# Reflectometer_Sheet.net
KiCad netlist of a schematic drawn in Altium Designer
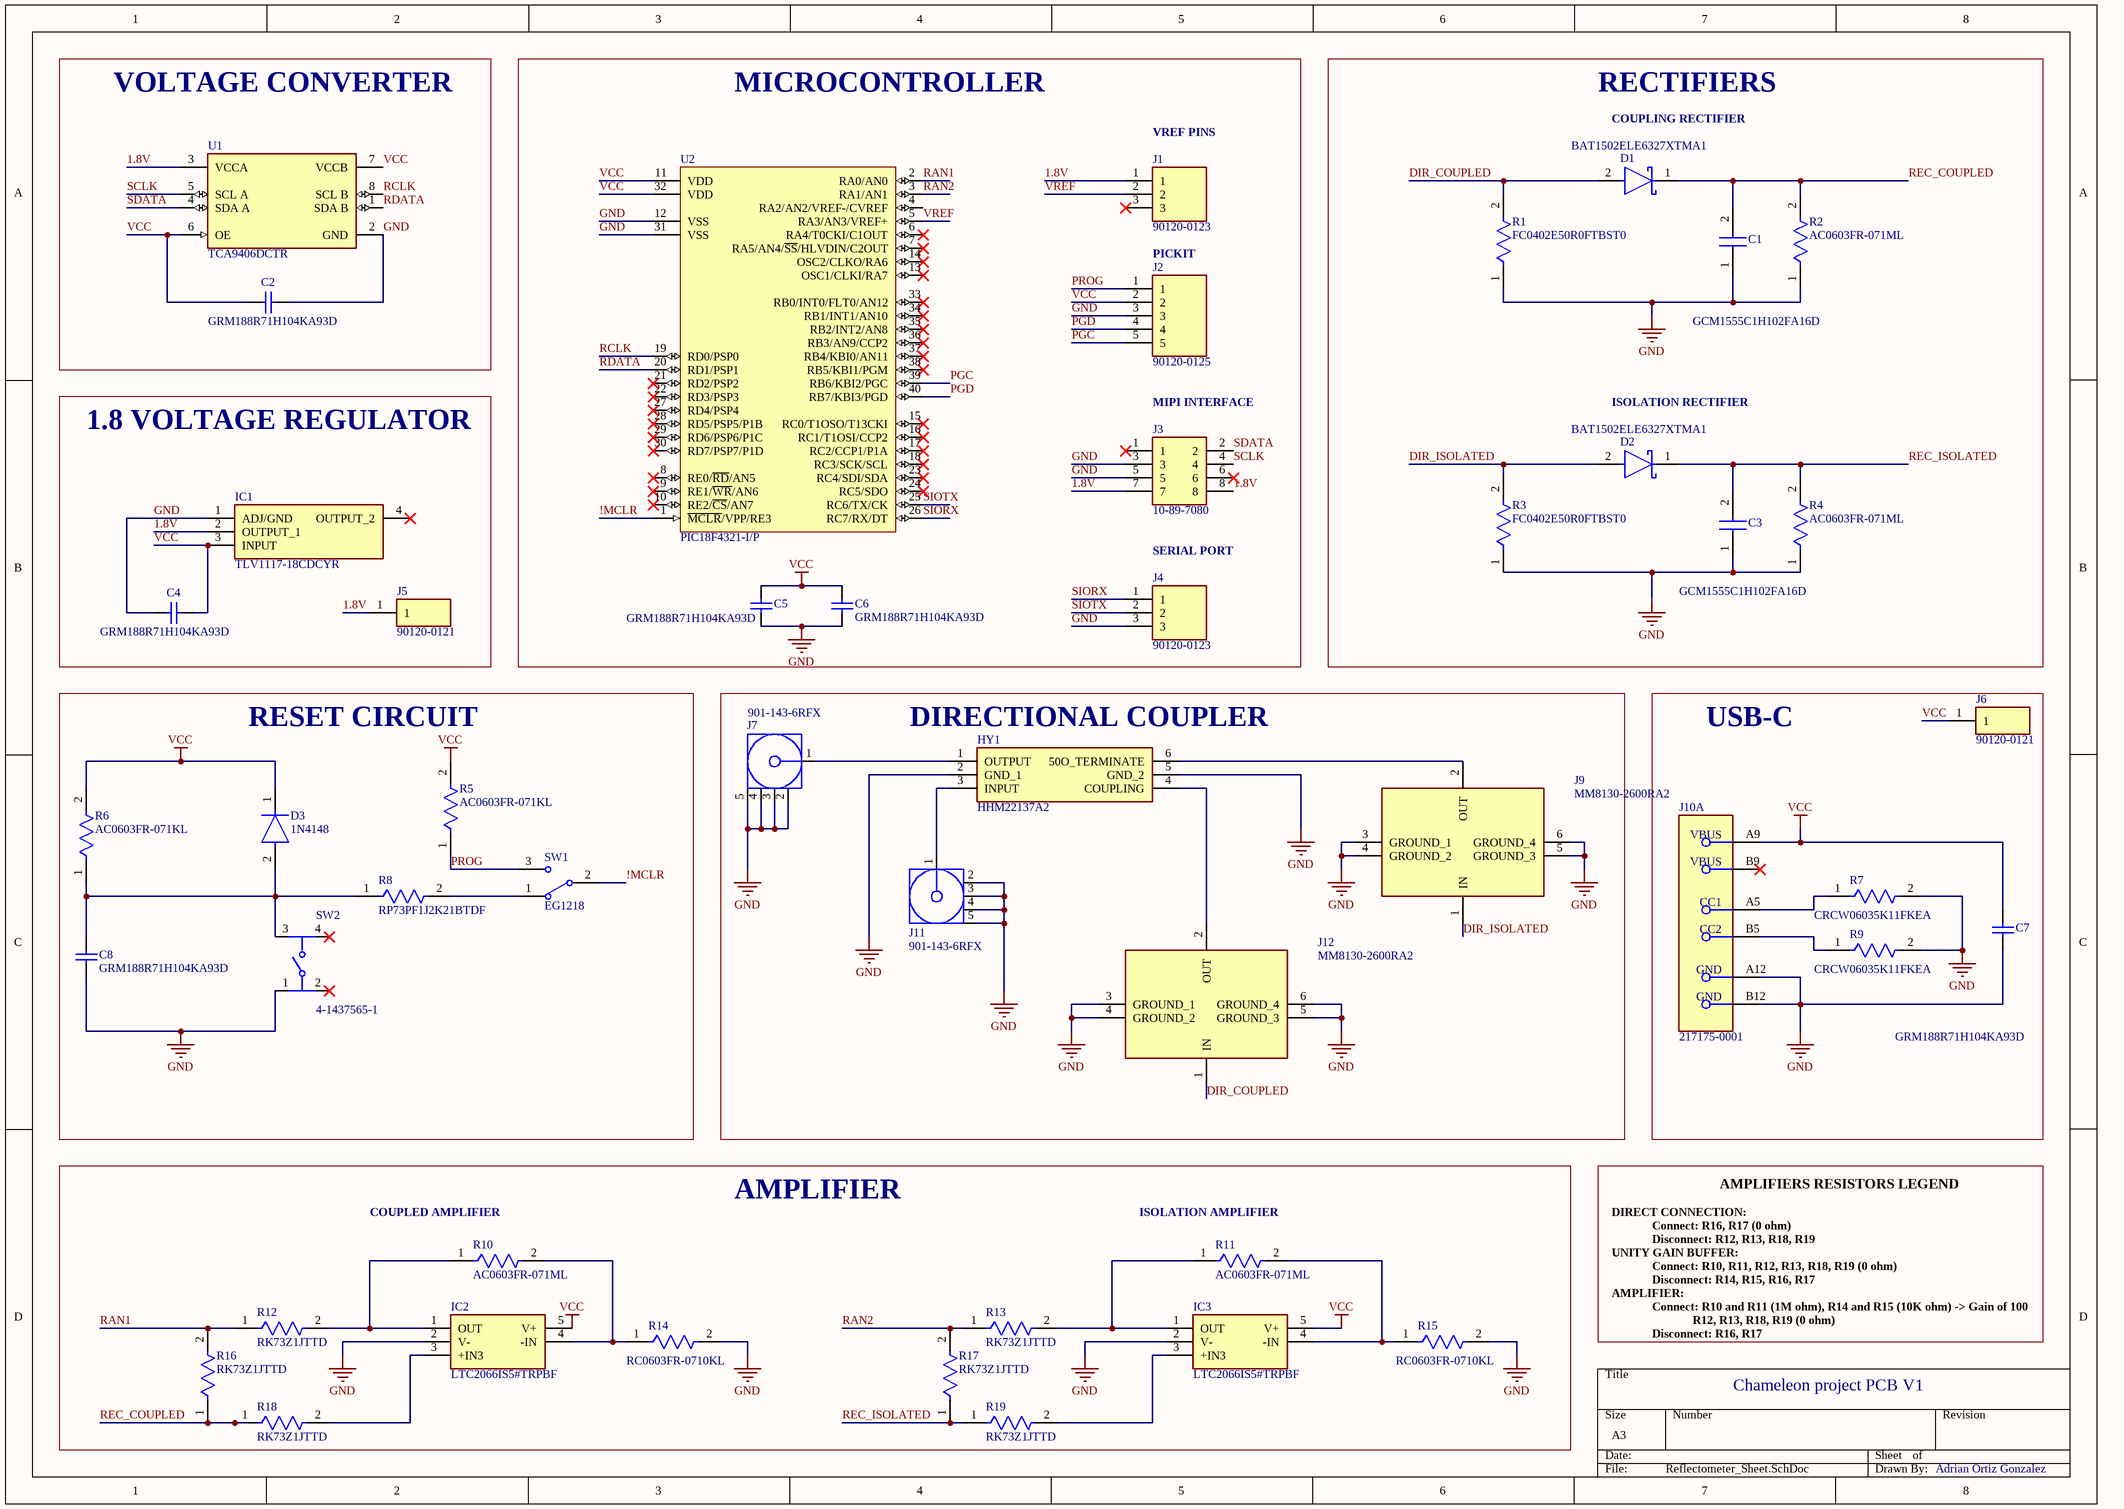
[diagram p0: Reflectometer_Sheet.SchDoc]

(export (version "E")
  (design (tool "Eeschema 10.0.6"))
  (components
    (comp (ref "C1")
      (value "GCM1555C1H102FA16D")
      (footprint "SamacSys:GCM155")
      (description "Capacitor")
      (fields (field (name "MOUSER PART NUMBER") "81-GCM1555C1H102FA6D"))
      (libsource (lib "*") (part "GCM1555C1H102FA16D"))
    )
    (comp (ref "C2")
      (value "GRM188R71H104KA93D")
      (footprint "CAPC1608X90X35ML10T15")
      (description "Chip Capacitor, 0.1 uF, +/- 10%, 50 V, -55 to 125 degC, 0603 (1608 Metric), RoHS, Tape and Reel")
      (fields (field (name "TOLERANCE") "10%") (field (name "VOLTAGE") "50V"))
      (libsource (lib "Altium Content Vault") (part "CAP-NP-2"))
    )
    (comp (ref "C3")
      (value "GCM1555C1H102FA16D")
      (footprint "SamacSys:GCM155")
      (description "Capacitor")
      (fields (field (name "MOUSER PART NUMBER") "81-GCM1555C1H102FA6D"))
      (libsource (lib "*") (part "GCM1555C1H102FA16D"))
    )
    (comp (ref "C4")
      (value "GRM188R71H104KA93D")
      (footprint "CAPC1608X90X35ML10T15")
      (description "Chip Capacitor, 0.1 uF, +/- 10%, 50 V, -55 to 125 degC, 0603 (1608 Metric), RoHS, Tape and Reel")
      (fields (field (name "TOLERANCE") "10%") (field (name "VOLTAGE") "50V"))
      (libsource (lib "Altium Content Vault") (part "CAP-NP-2"))
    )
    (comp (ref "C5")
      (value "GRM188R71H104KA93D")
      (footprint "CAPC1608X90X35ML10T15")
      (description "Chip Capacitor, 0.1 uF, +/- 10%, 50 V, -55 to 125 degC, 0603 (1608 Metric), RoHS, Tape and Reel")
      (fields (field (name "TOLERANCE") "10%") (field (name "VOLTAGE") "50V"))
      (libsource (lib "Altium Content Vault") (part "CAP-NP-2"))
    )
    (comp (ref "C6")
      (value "GRM188R71H104KA93D")
      (footprint "CAPC1608X90X35ML10T15")
      (description "Chip Capacitor, 0.1 uF, +/- 10%, 50 V, -55 to 125 degC, 0603 (1608 Metric), RoHS, Tape and Reel")
      (fields (field (name "TOLERANCE") "10%") (field (name "VOLTAGE") "50V"))
      (libsource (lib "Altium Content Vault") (part "CAP-NP-2"))
    )
    (comp (ref "C7")
      (value "GRM188R71H104KA93D")
      (footprint "CAPC1608X90X35ML10T15")
      (description "Chip Capacitor, 0.1 uF, +/- 10%, 50 V, -55 to 125 degC, 0603 (1608 Metric), RoHS, Tape and Reel")
      (fields (field (name "TOLERANCE") "10%") (field (name "VOLTAGE") "50V"))
      (libsource (lib "Altium Content Vault") (part "CAP-NP-2"))
    )
    (comp (ref "C8")
      (value "GRM188R71H104KA93D")
      (footprint "CAPC1608X90X35ML10T15")
      (description "Chip Capacitor, 0.1 uF, +/- 10%, 50 V, -55 to 125 degC, 0603 (1608 Metric), RoHS, Tape and Reel")
      (fields (field (name "TOLERANCE") "10%") (field (name "VOLTAGE") "50V"))
      (libsource (lib "Altium Content Vault") (part "CAP-NP-2"))
    )
    (comp (ref "D1")
      (value "BAT1502ELE6327XTMA1")
      (footprint "FP-PG-TSLP-2-MFG")
      (description "DIODE SCHOT 4V 110MA TSLP-2-19")
      (libsource (lib "Altium Content Vault") (part "1d6ec82d83fb6aee721767c19dac4b9"))
    )
    (comp (ref "D2")
      (value "BAT1502ELE6327XTMA1")
      (footprint "FP-PG-TSLP-2-MFG")
      (description "DIODE SCHOT 4V 110MA TSLP-2-19")
      (libsource (lib "Altium Content Vault") (part "1d6ec82d83fb6aee721767c19dac4b9"))
    )
    (comp (ref "D3")
      (value "1N4148")
      (footprint "FP-017AG-MFG")
      (description "DIODE GEN PURP 100V 200MA DO35")
      (fields (field (name "VOLTAGE") "100V"))
      (libsource (lib "Altium Content Vault") (part "d7152d700b627762746794eb795d46e"))
    )
    (comp (ref "HY1")
      (value "HHM22137A2")
      (footprint "SamacSys:HHM22137A2")
      (description "Circulator or Directional Coupler")
      (fields (field (name "MOUSER PART NUMBER") "810-HHM22137A2"))
      (libsource (lib "*") (part "HHM22137A2"))
    )
    (comp (ref "IC1")
      (value "TLV1117-18CDCYR")
      (footprint "SamacSys:SOT230P700X180-4N")
      (description "Integrated Circuit")
      (fields (field (name "MOUSER PART NUMBER") "595-TLV1117-18CDCYR"))
      (libsource (lib "*") (part "TLV1117-18CDCYR"))
    )
    (comp (ref "IC2")
      (value "LTC2066IS5#TRPBF")
      (footprint "SamacSys:LTC2066IS5TRPBF")
      (description "Integrated Circuit")
      (fields (field (name "MOUSER PART NUMBER") "584-LTC2066IS5TRPBF"))
      (libsource (lib "*") (part "LTC2066IS5#TRPBF"))
    )
    (comp (ref "IC3")
      (value "LTC2066IS5#TRPBF")
      (footprint "SamacSys:LTC2066IS5TRPBF")
      (description "Integrated Circuit")
      (fields (field (name "MOUSER PART NUMBER") "584-LTC2066IS5TRPBF"))
      (libsource (lib "*") (part "LTC2066IS5#TRPBF"))
    )
    (comp (ref "J1")
      (value "90120-0123")
      (footprint "SamacSys:HDRV3W90P0X254_1X3_762X249X560P")
      (description "Connector")
      (fields (field (name "MOUSER PART NUMBER") "538-90120-0123"))
      (libsource (lib "*") (part "90120-0123"))
    )
    (comp (ref "J2")
      (value "90120-0125")
      (footprint "SamacSys:HDRV5W90P0X254_1X5_1270X250X965P")
      (description "Connector")
      (fields (field (name "MOUSER PART NUMBER") "538-90120-0125"))
      (libsource (lib "*") (part "90120-0125"))
    )
    (comp (ref "J3")
      (value "10-89-7080")
      (footprint "SamacSys:HDRV8W87P254_2X4_1029X508X864P")
      (description "Connector")
      (fields (field (name "MOUSER PART NUMBER") "538-10-89-7080"))
      (libsource (lib "*") (part "10-89-7080"))
    )
    (comp (ref "J4")
      (value "90120-0123")
      (footprint "SamacSys:HDRV3W90P0X254_1X3_762X249X560P")
      (description "Connector")
      (fields (field (name "MOUSER PART NUMBER") "538-90120-0123"))
      (libsource (lib "*") (part "90120-0123"))
    )
    (comp (ref "J5")
      (value "90120-0121")
      (footprint "SamacSys:HDRV1W65P0X254_1X1_232X249X560P")
      (description "Connector")
      (fields (field (name "MOUSER PART NUMBER") "538-90120-0121"))
      (libsource (lib "*") (part "90120-0121"))
    )
    (comp (ref "J6")
      (value "90120-0121")
      (footprint "SamacSys:HDRV1W65P0X254_1X1_232X249X560P")
      (description "Connector")
      (fields (field (name "MOUSER PART NUMBER") "538-90120-0121"))
      (libsource (lib "*") (part "90120-0121"))
    )
    (comp (ref "J7")
      (value "901-143-6RFX")
      (footprint "AMPH-901-143-6RFX_V")
      (description "Coaxial connector, 50 Ohm, -65 to 165 degC, 5-Pin THD, RoHS, Bulk")
      (fields (field (name "MANUFACTURER") "Amphenol"))
      (libsource (lib "Altium Content Vault") (part "CN-S-4F-RF5"))
    )
    (comp (ref "J9")
      (value "MM8130-2600RA2")
      (footprint "SamacSys:MM81302600RA2")
      (description "Connector")
      (fields (field (name "MOUSER PART NUMBER") "81-MM8130-2600RA2"))
      (libsource (lib "*") (part "MM8130-2600RA2"))
    )
    (comp (ref "J10")
      (value "217175-0001")
      (footprint "FP-217175-0001-MFG")
      (description "CONN RCP USB2.0 C 6+18P SMD RA")
      (libsource (lib "Altium Content Vault") (part "6a66c69350f09309f94811689c98437"))
    )
    (comp (ref "J11")
      (value "901-143-6RFX")
      (footprint "AMPH-901-143-6RFX_V")
      (description "Coaxial connector, 50 Ohm, -65 to 165 degC, 5-Pin THD, RoHS, Bulk")
      (fields (field (name "MANUFACTURER") "Amphenol"))
      (libsource (lib "Altium Content Vault") (part "CN-S-4F-RF5"))
    )
    (comp (ref "J12")
      (value "MM8130-2600RA2")
      (footprint "SamacSys:MM81302600RA2")
      (description "Connector")
      (fields (field (name "MOUSER PART NUMBER") "81-MM8130-2600RA2"))
      (libsource (lib "*") (part "MM8130-2600RA2"))
    )
    (comp (ref "R1")
      (value "FC0402E50R0FTBST0")
      (footprint "FP-FC0402-MFG")
      (fields (field (name "TOLERANCE") "1%"))
      (libsource (lib "Altium Content Vault") (part "1029c3af85768c4190bb7ad29bc67b5"))
    )
    (comp (ref "R2")
      (value "AC0603FR-071ML")
      (footprint "FP-AC0603-IPC_C")
      (description "RES 1MΩ 1.00% 0.1W 0603")
      (fields (field (name "TOLERANCE") "1%"))
      (libsource (lib "Altium Content Vault") (part "1029c3af85768c4190bb7ad29bc67b5"))
    )
    (comp (ref "R3")
      (value "FC0402E50R0FTBST0")
      (footprint "FP-FC0402-MFG")
      (fields (field (name "TOLERANCE") "1%"))
      (libsource (lib "Altium Content Vault") (part "1029c3af85768c4190bb7ad29bc67b5"))
    )
    (comp (ref "R4")
      (value "AC0603FR-071ML")
      (footprint "FP-AC0603-IPC_C")
      (description "RES 1MΩ 1.00% 0.1W 0603")
      (fields (field (name "TOLERANCE") "1%"))
      (libsource (lib "Altium Content Vault") (part "1029c3af85768c4190bb7ad29bc67b5"))
    )
    (comp (ref "R5")
      (value "AC0603FR-071KL")
      (footprint "FP-AC0603-IPC_B")
      (description "RES 1kΩ 1.00% 0.1W 0603")
      (fields (field (name "TOLERANCE") "1%"))
      (libsource (lib "Altium Content Vault") (part "1029c3af85768c4190bb7ad29bc67b5"))
    )
    (comp (ref "R6")
      (value "AC0603FR-071KL")
      (footprint "FP-AC0603-IPC_B")
      (description "RES 1kΩ 1.00% 0.1W 0603")
      (fields (field (name "TOLERANCE") "1%"))
      (libsource (lib "Altium Content Vault") (part "1029c3af85768c4190bb7ad29bc67b5"))
    )
    (comp (ref "R7")
      (value "CRCW06035K11FKEA")
      (footprint "FP-CRCW0603-e3-IPC_B")
      (description "RES Thick Film, 5.11kΩ, 1%, 0.1W, 100ppm/°C, 0603")
      (fields (field (name "TOLERANCE") "1%"))
      (libsource (lib "Altium Content Vault") (part "1029c3af85768c4190bb7ad29bc67b5"))
    )
    (comp (ref "R8")
      (value "RP73PF1J2K21BTDF")
      (footprint "FP-RP73P-1J-MFG")
      (description "RES SMD 2.21K OHM 0.1% 1/6W 0603")
      (fields
        (field (name "MANUFACTURER") "TE Connectivity")
        (field (name "OCTOPART") "https://octopart.com/rp73pf1j2k21btdf-te+connectivity-23826919")
      )
      (libsource (lib "Altium Content Vault") (part "1029c3af85768c4190bb7ad29bc67b5"))
    )
    (comp (ref "R9")
      (value "CRCW06035K11FKEA")
      (footprint "FP-CRCW0603-e3-IPC_B")
      (description "RES Thick Film, 5.11kΩ, 1%, 0.1W, 100ppm/°C, 0603")
      (fields (field (name "TOLERANCE") "1%"))
      (libsource (lib "Altium Content Vault") (part "1029c3af85768c4190bb7ad29bc67b5"))
    )
    (comp (ref "R10")
      (value "AC0603FR-071ML")
      (footprint "FP-AC0603-IPC_C")
      (description "RES 1MΩ 1.00% 0.1W 0603")
      (fields (field (name "TOLERANCE") "1%"))
      (libsource (lib "Altium Content Vault") (part "1029c3af85768c4190bb7ad29bc67b5"))
    )
    (comp (ref "R11")
      (value "AC0603FR-071ML")
      (footprint "FP-AC0603-IPC_C")
      (description "RES 1MΩ 1.00% 0.1W 0603")
      (fields (field (name "TOLERANCE") "1%"))
      (libsource (lib "Altium Content Vault") (part "1029c3af85768c4190bb7ad29bc67b5"))
    )
    (comp (ref "R12")
      (value "RK73Z1JTTD")
      (footprint "FP-RK73Z1J-MFG")
      (description "RES 0 OHM JUMPER 0603")
      (fields (field (name "TOLERANCE") "1%"))
      (libsource (lib "Altium Content Vault") (part "1029c3af85768c4190bb7ad29bc67b5"))
    )
    (comp (ref "R13")
      (value "RK73Z1JTTD")
      (footprint "FP-RK73Z1J-MFG")
      (description "RES 0 OHM JUMPER 0603")
      (fields (field (name "TOLERANCE") "1%"))
      (libsource (lib "Altium Content Vault") (part "1029c3af85768c4190bb7ad29bc67b5"))
    )
    (comp (ref "R14")
      (value "RC0603FR-0710KL")
      (footprint "FP-RC0603-0_55-IPC_C")
      (description "RES 10K OHM 1% 1/10W 0603")
      (fields (field (name "TOLERANCE") "1%"))
      (libsource (lib "Altium Content Vault") (part "1029c3af85768c4190bb7ad29bc67b5"))
    )
    (comp (ref "R15")
      (value "RC0603FR-0710KL")
      (footprint "FP-RC0603-0_55-IPC_C")
      (description "RES 10K OHM 1% 1/10W 0603")
      (fields (field (name "TOLERANCE") "1%"))
      (libsource (lib "Altium Content Vault") (part "1029c3af85768c4190bb7ad29bc67b5"))
    )
    (comp (ref "R16")
      (value "RK73Z1JTTD")
      (footprint "FP-RK73Z1J-MFG")
      (description "RES 0 OHM JUMPER 0603")
      (fields (field (name "TOLERANCE") "1%"))
      (libsource (lib "Altium Content Vault") (part "1029c3af85768c4190bb7ad29bc67b5"))
    )
    (comp (ref "R17")
      (value "RK73Z1JTTD")
      (footprint "FP-RK73Z1J-MFG")
      (description "RES 0 OHM JUMPER 0603")
      (fields (field (name "TOLERANCE") "1%"))
      (libsource (lib "Altium Content Vault") (part "1029c3af85768c4190bb7ad29bc67b5"))
    )
    (comp (ref "R18")
      (value "RK73Z1JTTD")
      (footprint "FP-RK73Z1J-MFG")
      (description "RES 0 OHM JUMPER 0603")
      (fields (field (name "TOLERANCE") "1%"))
      (libsource (lib "Altium Content Vault") (part "1029c3af85768c4190bb7ad29bc67b5"))
    )
    (comp (ref "R19")
      (value "RK73Z1JTTD")
      (footprint "FP-RK73Z1J-MFG")
      (description "RES 0 OHM JUMPER 0603")
      (fields (field (name "TOLERANCE") "1%"))
      (libsource (lib "Altium Content Vault") (part "1029c3af85768c4190bb7ad29bc67b5"))
    )
    (comp (ref "SW1")
      (value "EG1218")
      (footprint "ESWI-EG1218_V")
      (description "Slide Switch, 500 V, -20 to 70 degC, 3-Pin THD, RoHS")
      (libsource (lib "Altium Content Vault") (part "SW-SPDT-3_B"))
    )
    (comp (ref "SW2")
      (value "4-1437565-1")
      (footprint "FP-4-1437565-1-MFG")
      (description "SWITCH TACTILE SPST-NO 0.05A 24V")
      (fields
        (field (name "MANUFACTURER") "TE Connectivity")
        (field (name "OCTOPART") "https://octopart.com/fsm4jsma-te+connectivity-55488004")
      )
      (libsource (lib "Altium Content Vault") (part "b8895f3f4cefb76e1819d2863dba89b"))
    )
    (comp (ref "U1")
      (value "TCA9406DCTR")
      (footprint "FP-DCT0008A-MFG")
      (description "IC TRNSLTR BIDIRECTIONAL SM8")
      (libsource (lib "Altium Content Vault") (part "3f41b918c53748b0080b1005cc648b3"))
    )
    (comp (ref "U2")
      (value "PIC18F4321-I/P")
      (footprint "PDIP600-P40")
      (libsource (lib "Altium Content Vault") (part "MC-8B-18F4321-IL40"))
    )
  )
  (nets
    (net (code "1") (name "/!MCLR") (class "Default")
      (node (ref "SW1") (pin "2") (pinfunction "COM_2") (pintype "passive"))
      (node (ref "U2") (pin "1") (pinfunction "~{MCLR}/VPP/RE3_1") (pintype "input"))
    )
    (net (code "2") (name "/1.8V") (class "Default")
      (node (ref "IC1") (pin "2") (pinfunction "OUTPUT_1_2") (pintype "passive"))
      (node (ref "J1") (pin "1") (pinfunction "1_1") (pintype "passive"))
      (node (ref "J3") (pin "7") (pinfunction "7_7") (pintype "passive"))
      (node (ref "J3") (pin "8") (pinfunction "8_8") (pintype "passive"))
      (node (ref "J5") (pin "1") (pinfunction "1_1") (pintype "passive"))
      (node (ref "U1") (pin "3") (pinfunction "VCCA_3") (pintype "power_in"))
    )
    (net (code "3") (name "/DIR_COUPLED") (class "Default")
      (node (ref "D1") (pin "2") (pinfunction "A_2") (pintype "passive"))
      (node (ref "J12") (pin "1") (pinfunction "IN_1") (pintype "passive"))
      (node (ref "R1") (pin "2") (pinfunction "2_2") (pintype "passive"))
    )
    (net (code "4") (name "/DIR_ISOLATED") (class "Default")
      (node (ref "D2") (pin "2") (pinfunction "A_2") (pintype "passive"))
      (node (ref "J9") (pin "1") (pinfunction "IN_1") (pintype "passive"))
      (node (ref "R3") (pin "2") (pinfunction "2_2") (pintype "passive"))
    )
    (net (code "5") (name "/PGC") (class "Default")
      (node (ref "J2") (pin "5") (pinfunction "5_5") (pintype "passive"))
      (node (ref "U2") (pin "39") (pinfunction "RB6/KBI2/PGC_39") (pintype "bidirectional"))
    )
    (net (code "6") (name "/PGD") (class "Default")
      (node (ref "J2") (pin "4") (pinfunction "4_4") (pintype "passive"))
      (node (ref "U2") (pin "40") (pinfunction "RB7/KBI3/PGD_40") (pintype "bidirectional"))
    )
    (net (code "7") (name "/PROG") (class "Default")
      (node (ref "J2") (pin "1") (pinfunction "1_1") (pintype "passive"))
      (node (ref "R5") (pin "1") (pinfunction "1_1") (pintype "passive"))
      (node (ref "SW1") (pin "3") (pinfunction "3_3") (pintype "passive"))
    )
    (net (code "8") (name "/RAN1") (class "Default")
      (node (ref "R12") (pin "1") (pinfunction "1_1") (pintype "passive"))
      (node (ref "R16") (pin "2") (pinfunction "2_2") (pintype "passive"))
      (node (ref "U2") (pin "2") (pinfunction "RA0/AN0_2") (pintype "bidirectional"))
    )
    (net (code "9") (name "/RAN2") (class "Default")
      (node (ref "R13") (pin "1") (pinfunction "1_1") (pintype "passive"))
      (node (ref "R17") (pin "2") (pinfunction "2_2") (pintype "passive"))
      (node (ref "U2") (pin "3") (pinfunction "RA1/AN1_3") (pintype "bidirectional"))
    )
    (net (code "10") (name "/RCLK") (class "Default")
      (node (ref "U1") (pin "8") (pinfunction "SCL_B_8") (pintype "bidirectional"))
      (node (ref "U2") (pin "19") (pinfunction "RD0/PSP0_19") (pintype "bidirectional"))
    )
    (net (code "11") (name "/RDATA") (class "Default")
      (node (ref "U1") (pin "1") (pinfunction "SDA_B_1") (pintype "bidirectional"))
      (node (ref "U2") (pin "20") (pinfunction "RD1/PSP1_20") (pintype "bidirectional"))
    )
    (net (code "12") (name "/REC_COUPLED") (class "Default")
      (node (ref "C1") (pin "2") (pinfunction "2_2") (pintype "passive"))
      (node (ref "D1") (pin "1") (pinfunction "C_1") (pintype "passive"))
      (node (ref "R16") (pin "1") (pinfunction "1_1") (pintype "passive"))
      (node (ref "R18") (pin "1") (pinfunction "1_1") (pintype "passive"))
      (node (ref "R2") (pin "2") (pinfunction "2_2") (pintype "passive"))
    )
    (net (code "13") (name "/REC_ISOLATED") (class "Default")
      (node (ref "C3") (pin "2") (pinfunction "2_2") (pintype "passive"))
      (node (ref "D2") (pin "1") (pinfunction "C_1") (pintype "passive"))
      (node (ref "R17") (pin "1") (pinfunction "1_1") (pintype "passive"))
      (node (ref "R19") (pin "1") (pinfunction "1_1") (pintype "passive"))
      (node (ref "R4") (pin "2") (pinfunction "2_2") (pintype "passive"))
    )
    (net (code "14") (name "/SCLK") (class "Default")
      (node (ref "J3") (pin "4") (pinfunction "4_4") (pintype "passive"))
      (node (ref "U1") (pin "5") (pinfunction "SCL_A_5") (pintype "bidirectional"))
    )
    (net (code "15") (name "/SDATA") (class "Default")
      (node (ref "J3") (pin "2") (pinfunction "2_2") (pintype "passive"))
      (node (ref "U1") (pin "4") (pinfunction "SDA_A_4") (pintype "bidirectional"))
    )
    (net (code "16") (name "/SIORX") (class "Default")
      (node (ref "J4") (pin "1") (pinfunction "1_1") (pintype "passive"))
      (node (ref "U2") (pin "26") (pinfunction "RC7/RX/DT_26") (pintype "bidirectional"))
    )
    (net (code "17") (name "/SIOTX") (class "Default")
      (node (ref "J4") (pin "2") (pinfunction "2_2") (pintype "passive"))
      (node (ref "U2") (pin "25") (pinfunction "RC6/TX/CK_25") (pintype "bidirectional"))
    )
    (net (code "18") (name "/VREF") (class "Default")
      (node (ref "J1") (pin "2") (pinfunction "2_2") (pintype "passive"))
      (node (ref "U2") (pin "5") (pinfunction "RA3/AN3/VREF+_5") (pintype "bidirectional"))
    )
    (net (code "19") (name "GND") (class "Default")
      (node (ref "C1") (pin "1") (pinfunction "1_1") (pintype "passive"))
      (node (ref "C2") (pin "2") (pinfunction "2_2") (pintype "passive"))
      (node (ref "C3") (pin "1") (pinfunction "1_1") (pintype "passive"))
      (node (ref "C4") (pin "1") (pinfunction "1_1") (pintype "passive"))
      (node (ref "C5") (pin "1") (pinfunction "1_1") (pintype "passive"))
      (node (ref "C6") (pin "1") (pinfunction "1_1") (pintype "passive"))
      (node (ref "C7") (pin "1") (pinfunction "1_1") (pintype "passive"))
      (node (ref "C8") (pin "1") (pinfunction "1_1") (pintype "passive"))
      (node (ref "HY1") (pin "2") (pinfunction "GND_1_2") (pintype "passive"))
      (node (ref "HY1") (pin "5") (pinfunction "GND_2_5") (pintype "passive"))
      (node (ref "IC1") (pin "1") (pinfunction "ADJ/GND_1") (pintype "passive"))
      (node (ref "IC2") (pin "2") (pinfunction "V-_2") (pintype "passive"))
      (node (ref "IC3") (pin "2") (pinfunction "V-_2") (pintype "passive"))
      (node (ref "J10") (pin "A12") (pinfunction "GND_A12") (pintype "power_in"))
      (node (ref "J10") (pin "B12") (pinfunction "GND_B12") (pintype "power_in"))
      (node (ref "J11") (pin "2") (pinfunction "2_2") (pintype "passive"))
      (node (ref "J11") (pin "3") (pinfunction "3_3") (pintype "passive"))
      (node (ref "J11") (pin "4") (pinfunction "4_4") (pintype "passive"))
      (node (ref "J11") (pin "5") (pinfunction "5_5") (pintype "passive"))
      (node (ref "J12") (pin "3") (pinfunction "GROUND_1_3") (pintype "passive"))
      (node (ref "J12") (pin "4") (pinfunction "GROUND_2_4") (pintype "passive"))
      (node (ref "J12") (pin "5") (pinfunction "GROUND_3_5") (pintype "passive"))
      (node (ref "J12") (pin "6") (pinfunction "GROUND_4_6") (pintype "passive"))
      (node (ref "J2") (pin "3") (pinfunction "3_3") (pintype "passive"))
      (node (ref "J3") (pin "3") (pinfunction "3_3") (pintype "passive"))
      (node (ref "J3") (pin "5") (pinfunction "5_5") (pintype "passive"))
      (node (ref "J4") (pin "3") (pinfunction "3_3") (pintype "passive"))
      (node (ref "J7") (pin "2") (pinfunction "2_2") (pintype "passive"))
      (node (ref "J7") (pin "3") (pinfunction "3_3") (pintype "passive"))
      (node (ref "J7") (pin "4") (pinfunction "4_4") (pintype "passive"))
      (node (ref "J7") (pin "5") (pinfunction "5_5") (pintype "passive"))
      (node (ref "J9") (pin "3") (pinfunction "GROUND_1_3") (pintype "passive"))
      (node (ref "J9") (pin "4") (pinfunction "GROUND_2_4") (pintype "passive"))
      (node (ref "J9") (pin "5") (pinfunction "GROUND_3_5") (pintype "passive"))
      (node (ref "J9") (pin "6") (pinfunction "GROUND_4_6") (pintype "passive"))
      (node (ref "R1") (pin "1") (pinfunction "1_1") (pintype "passive"))
      (node (ref "R14") (pin "2") (pinfunction "2_2") (pintype "passive"))
      (node (ref "R15") (pin "2") (pinfunction "2_2") (pintype "passive"))
      (node (ref "R2") (pin "1") (pinfunction "1_1") (pintype "passive"))
      (node (ref "R3") (pin "1") (pinfunction "1_1") (pintype "passive"))
      (node (ref "R4") (pin "1") (pinfunction "1_1") (pintype "passive"))
      (node (ref "R7") (pin "2") (pinfunction "2_2") (pintype "passive"))
      (node (ref "R9") (pin "2") (pinfunction "2_2") (pintype "passive"))
      (node (ref "SW2") (pin "1") (pinfunction "1_1") (pintype "passive"))
      (node (ref "U1") (pin "2") (pinfunction "GND_2") (pintype "power_in"))
      (node (ref "U2") (pin "12") (pinfunction "VSS_12") (pintype "power_in"))
      (node (ref "U2") (pin "31") (pinfunction "VSS_31") (pintype "power_in"))
    )
    (net (code "20") (name "Net-(D3-A)") (class "Default")
      (node (ref "C8") (pin "2") (pinfunction "2_2") (pintype "passive"))
      (node (ref "D3") (pin "2") (pinfunction "A_2") (pintype "passive"))
      (node (ref "R6") (pin "1") (pinfunction "1_1") (pintype "passive"))
      (node (ref "R8") (pin "1") (pinfunction "1_1") (pintype "passive"))
      (node (ref "SW2") (pin "3") (pinfunction "3_3") (pintype "passive"))
    )
    (net (code "21") (name "Net-(HY1-50O_TERMINATE)") (class "Default")
      (node (ref "HY1") (pin "6") (pinfunction "50O_TERMINATE_6") (pintype "passive"))
      (node (ref "J9") (pin "2") (pinfunction "OUT_2") (pintype "passive"))
    )
    (net (code "22") (name "Net-(HY1-COUPLING)") (class "Default")
      (node (ref "HY1") (pin "4") (pinfunction "COUPLING_4") (pintype "passive"))
      (node (ref "J12") (pin "2") (pinfunction "OUT_2") (pintype "passive"))
    )
    (net (code "23") (name "Net-(HY1-INPUT)") (class "Default")
      (node (ref "HY1") (pin "3") (pinfunction "INPUT_3") (pintype "passive"))
      (node (ref "J11") (pin "1") (pinfunction "1_1") (pintype "passive"))
    )
    (net (code "24") (name "Net-(HY1-OUTPUT)") (class "Default")
      (node (ref "HY1") (pin "1") (pinfunction "OUTPUT_1") (pintype "passive"))
      (node (ref "J7") (pin "1") (pinfunction "1_1") (pintype "passive"))
    )
    (net (code "25") (name "Net-(IC2-+IN3)") (class "Default")
      (node (ref "IC2") (pin "3") (pinfunction "+IN3_3") (pintype "passive"))
      (node (ref "R18") (pin "2") (pinfunction "2_2") (pintype "passive"))
    )
    (net (code "26") (name "Net-(IC2--IN)") (class "Default")
      (node (ref "IC2") (pin "4") (pinfunction "-IN_4") (pintype "passive"))
      (node (ref "R10") (pin "2") (pinfunction "2_2") (pintype "passive"))
      (node (ref "R14") (pin "1") (pinfunction "1_1") (pintype "passive"))
    )
    (net (code "27") (name "Net-(IC2-OUT)") (class "Default")
      (node (ref "IC2") (pin "1") (pinfunction "OUT_1") (pintype "passive"))
      (node (ref "R10") (pin "1") (pinfunction "1_1") (pintype "passive"))
      (node (ref "R12") (pin "2") (pinfunction "2_2") (pintype "passive"))
    )
    (net (code "28") (name "Net-(IC3-+IN3)") (class "Default")
      (node (ref "IC3") (pin "3") (pinfunction "+IN3_3") (pintype "passive"))
      (node (ref "R19") (pin "2") (pinfunction "2_2") (pintype "passive"))
    )
    (net (code "29") (name "Net-(IC3--IN)") (class "Default")
      (node (ref "IC3") (pin "4") (pinfunction "-IN_4") (pintype "passive"))
      (node (ref "R11") (pin "2") (pinfunction "2_2") (pintype "passive"))
      (node (ref "R15") (pin "1") (pinfunction "1_1") (pintype "passive"))
    )
    (net (code "30") (name "Net-(IC3-OUT)") (class "Default")
      (node (ref "IC3") (pin "1") (pinfunction "OUT_1") (pintype "passive"))
      (node (ref "R11") (pin "1") (pinfunction "1_1") (pintype "passive"))
      (node (ref "R13") (pin "2") (pinfunction "2_2") (pintype "passive"))
    )
    (net (code "31") (name "Net-(J10A-CC1)") (class "Default")
      (node (ref "J10") (pin "A5") (pinfunction "CC1_A5") (pintype "passive"))
      (node (ref "R7") (pin "1") (pinfunction "1_1") (pintype "passive"))
    )
    (net (code "32") (name "Net-(J10A-CC2)") (class "Default")
      (node (ref "J10") (pin "B5") (pinfunction "CC2_B5") (pintype "passive"))
      (node (ref "R9") (pin "1") (pinfunction "1_1") (pintype "passive"))
    )
    (net (code "33") (name "Net-(R8-Pad2)") (class "Default")
      (node (ref "R8") (pin "2") (pinfunction "2_2") (pintype "passive"))
      (node (ref "SW1") (pin "1") (pinfunction "1_1") (pintype "passive"))
    )
    (net (code "34") (name "VCC") (class "Default")
      (node (ref "C2") (pin "1") (pinfunction "1_1") (pintype "passive"))
      (node (ref "C4") (pin "2") (pinfunction "2_2") (pintype "passive"))
      (node (ref "C5") (pin "2") (pinfunction "2_2") (pintype "passive"))
      (node (ref "C6") (pin "2") (pinfunction "2_2") (pintype "passive"))
      (node (ref "C7") (pin "2") (pinfunction "2_2") (pintype "passive"))
      (node (ref "D3") (pin "1") (pinfunction "C_1") (pintype "passive"))
      (node (ref "IC1") (pin "3") (pinfunction "INPUT_3") (pintype "passive"))
      (node (ref "IC2") (pin "5") (pinfunction "V+_5") (pintype "passive"))
      (node (ref "IC3") (pin "5") (pinfunction "V+_5") (pintype "passive"))
      (node (ref "J10") (pin "A9") (pinfunction "VBUS_A9") (pintype "power_in"))
      (node (ref "J2") (pin "2") (pinfunction "2_2") (pintype "passive"))
      (node (ref "J6") (pin "1") (pinfunction "1_1") (pintype "passive"))
      (node (ref "R5") (pin "2") (pinfunction "2_2") (pintype "passive"))
      (node (ref "R6") (pin "2") (pinfunction "2_2") (pintype "passive"))
      (node (ref "U1") (pin "6") (pinfunction "OE_6") (pintype "input"))
      (node (ref "U1") (pin "7") (pinfunction "VCCB_7") (pintype "power_in"))
      (node (ref "U2") (pin "11") (pinfunction "VDD_11") (pintype "power_in"))
      (node (ref "U2") (pin "32") (pinfunction "VDD_32") (pintype "power_in"))
    )
    (net (code "35") (name "unconnected-(IC1-OUTPUT_2-Pad4)") (class "Default")
      (node (ref "IC1") (pin "4") (pinfunction "OUTPUT_2_4") (pintype "passive+no_connect"))
    )
    (net (code "36") (name "unconnected-(J1-Pad3)") (class "Default")
      (node (ref "J1") (pin "3") (pinfunction "3_3") (pintype "passive+no_connect"))
    )
    (net (code "37") (name "unconnected-(J3-Pad1)") (class "Default")
      (node (ref "J3") (pin "1") (pinfunction "1_1") (pintype "passive+no_connect"))
    )
    (net (code "38") (name "unconnected-(J3-Pad6)") (class "Default")
      (node (ref "J3") (pin "6") (pinfunction "6_6") (pintype "passive+no_connect"))
    )
    (net (code "39") (name "unconnected-(J10A-VBUS-PadB9)") (class "Default")
      (node (ref "J10") (pin "B9") (pinfunction "VBUS_B9") (pintype "power_in+no_connect"))
    )
    (net (code "40") (name "unconnected-(SW2-Pad2)") (class "Default")
      (node (ref "SW2") (pin "2") (pinfunction "2_2") (pintype "passive+no_connect"))
    )
    (net (code "41") (name "unconnected-(SW2-Pad4)") (class "Default")
      (node (ref "SW2") (pin "4") (pinfunction "4_4") (pintype "passive+no_connect"))
    )
    (net (code "42") (name "unconnected-(U2-OSC1{slash}CLKI{slash}RA7-Pad13)") (class "Default")
      (node (ref "U2") (pin "13") (pinfunction "OSC1/CLKI/RA7_13") (pintype "bidirectional+no_connect"))
    )
    (net (code "43") (name "unconnected-(U2-OSC2{slash}CLKO{slash}RA6-Pad14)") (class "Default")
      (node (ref "U2") (pin "14") (pinfunction "OSC2/CLKO/RA6_14") (pintype "bidirectional+no_connect"))
    )
    (net (code "44") (name "unconnected-(U2-RA2{slash}AN2{slash}VREF-{slash}CVREF-Pad4)") (class "Default")
      (node (ref "U2") (pin "4") (pinfunction "RA2/AN2/VREF-/CVREF_4") (pintype "bidirectional"))
    )
    (net (code "45") (name "unconnected-(U2-RA4{slash}T0CKI{slash}C1OUT-Pad6)") (class "Default")
      (node (ref "U2") (pin "6") (pinfunction "RA4/T0CKI/C1OUT_6") (pintype "bidirectional+no_connect"))
    )
    (net (code "46") (name "unconnected-(U2-RA5{slash}AN4{slash}~{SS}{slash}HLVDIN{slash}C2OUT-Pad7)") (class "Default")
      (node (ref "U2") (pin "7") (pinfunction "RA5/AN4/~{SS}/HLVDIN/C2OUT_7") (pintype "bidirectional+no_connect"))
    )
    (net (code "47") (name "unconnected-(U2-RB0{slash}INT0{slash}FLT0{slash}AN12-Pad33)") (class "Default")
      (node (ref "U2") (pin "33") (pinfunction "RB0/INT0/FLT0/AN12_33") (pintype "bidirectional+no_connect"))
    )
    (net (code "48") (name "unconnected-(U2-RB1{slash}INT1{slash}AN10-Pad34)") (class "Default")
      (node (ref "U2") (pin "34") (pinfunction "RB1/INT1/AN10_34") (pintype "bidirectional+no_connect"))
    )
    (net (code "49") (name "unconnected-(U2-RB2{slash}INT2{slash}AN8-Pad35)") (class "Default")
      (node (ref "U2") (pin "35") (pinfunction "RB2/INT2/AN8_35") (pintype "bidirectional+no_connect"))
    )
    (net (code "50") (name "unconnected-(U2-RB3{slash}AN9{slash}CCP2-Pad36)") (class "Default")
      (node (ref "U2") (pin "36") (pinfunction "RB3/AN9/CCP2_36") (pintype "bidirectional+no_connect"))
    )
    (net (code "51") (name "unconnected-(U2-RB4{slash}KBI0{slash}AN11-Pad37)") (class "Default")
      (node (ref "U2") (pin "37") (pinfunction "RB4/KBI0/AN11_37") (pintype "bidirectional+no_connect"))
    )
    (net (code "52") (name "unconnected-(U2-RB5{slash}KBI1{slash}PGM-Pad38)") (class "Default")
      (node (ref "U2") (pin "38") (pinfunction "RB5/KBI1/PGM_38") (pintype "bidirectional+no_connect"))
    )
    (net (code "53") (name "unconnected-(U2-RC0{slash}T1OSO{slash}T13CKI-Pad15)") (class "Default")
      (node (ref "U2") (pin "15") (pinfunction "RC0/T1OSO/T13CKI_15") (pintype "bidirectional+no_connect"))
    )
    (net (code "54") (name "unconnected-(U2-RC1{slash}T1OSI{slash}CCP2-Pad16)") (class "Default")
      (node (ref "U2") (pin "16") (pinfunction "RC1/T1OSI/CCP2_16") (pintype "bidirectional+no_connect"))
    )
    (net (code "55") (name "unconnected-(U2-RC2{slash}CCP1{slash}P1A-Pad17)") (class "Default")
      (node (ref "U2") (pin "17") (pinfunction "RC2/CCP1/P1A_17") (pintype "bidirectional+no_connect"))
    )
    (net (code "56") (name "unconnected-(U2-RC3{slash}SCK{slash}SCL-Pad18)") (class "Default")
      (node (ref "U2") (pin "18") (pinfunction "RC3/SCK/SCL_18") (pintype "bidirectional+no_connect"))
    )
    (net (code "57") (name "unconnected-(U2-RC4{slash}SDI{slash}SDA-Pad23)") (class "Default")
      (node (ref "U2") (pin "23") (pinfunction "RC4/SDI/SDA_23") (pintype "bidirectional+no_connect"))
    )
    (net (code "58") (name "unconnected-(U2-RC5{slash}SDO-Pad24)") (class "Default")
      (node (ref "U2") (pin "24") (pinfunction "RC5/SDO_24") (pintype "bidirectional+no_connect"))
    )
    (net (code "59") (name "unconnected-(U2-RD2{slash}PSP2-Pad21)") (class "Default")
      (node (ref "U2") (pin "21") (pinfunction "RD2/PSP2_21") (pintype "bidirectional+no_connect"))
    )
    (net (code "60") (name "unconnected-(U2-RD3{slash}PSP3-Pad22)") (class "Default")
      (node (ref "U2") (pin "22") (pinfunction "RD3/PSP3_22") (pintype "bidirectional+no_connect"))
    )
    (net (code "61") (name "unconnected-(U2-RD4{slash}PSP4-Pad27)") (class "Default")
      (node (ref "U2") (pin "27") (pinfunction "RD4/PSP4_27") (pintype "bidirectional+no_connect"))
    )
    (net (code "62") (name "unconnected-(U2-RD5{slash}PSP5{slash}P1B-Pad28)") (class "Default")
      (node (ref "U2") (pin "28") (pinfunction "RD5/PSP5/P1B_28") (pintype "bidirectional+no_connect"))
    )
    (net (code "63") (name "unconnected-(U2-RD6{slash}PSP6{slash}P1C-Pad29)") (class "Default")
      (node (ref "U2") (pin "29") (pinfunction "RD6/PSP6/P1C_29") (pintype "bidirectional+no_connect"))
    )
    (net (code "64") (name "unconnected-(U2-RD7{slash}PSP7{slash}P1D-Pad30)") (class "Default")
      (node (ref "U2") (pin "30") (pinfunction "RD7/PSP7/P1D_30") (pintype "bidirectional+no_connect"))
    )
    (net (code "65") (name "unconnected-(U2-RE0{slash}~{RD}{slash}AN5-Pad8)") (class "Default")
      (node (ref "U2") (pin "8") (pinfunction "RE0/~{RD}/AN5_8") (pintype "bidirectional+no_connect"))
    )
    (net (code "66") (name "unconnected-(U2-RE1{slash}~{WR}{slash}AN6-Pad9)") (class "Default")
      (node (ref "U2") (pin "9") (pinfunction "RE1/~{WR}/AN6_9") (pintype "bidirectional+no_connect"))
    )
    (net (code "67") (name "unconnected-(U2-RE2{slash}~{CS}{slash}AN7-Pad10)") (class "Default")
      (node (ref "U2") (pin "10") (pinfunction "RE2/~{CS}/AN7_10") (pintype "bidirectional+no_connect"))
    )
  )
)
